# Spectroscilloscope_Revised_7.net
KiCad netlist of a schematic drawn in EAGLE
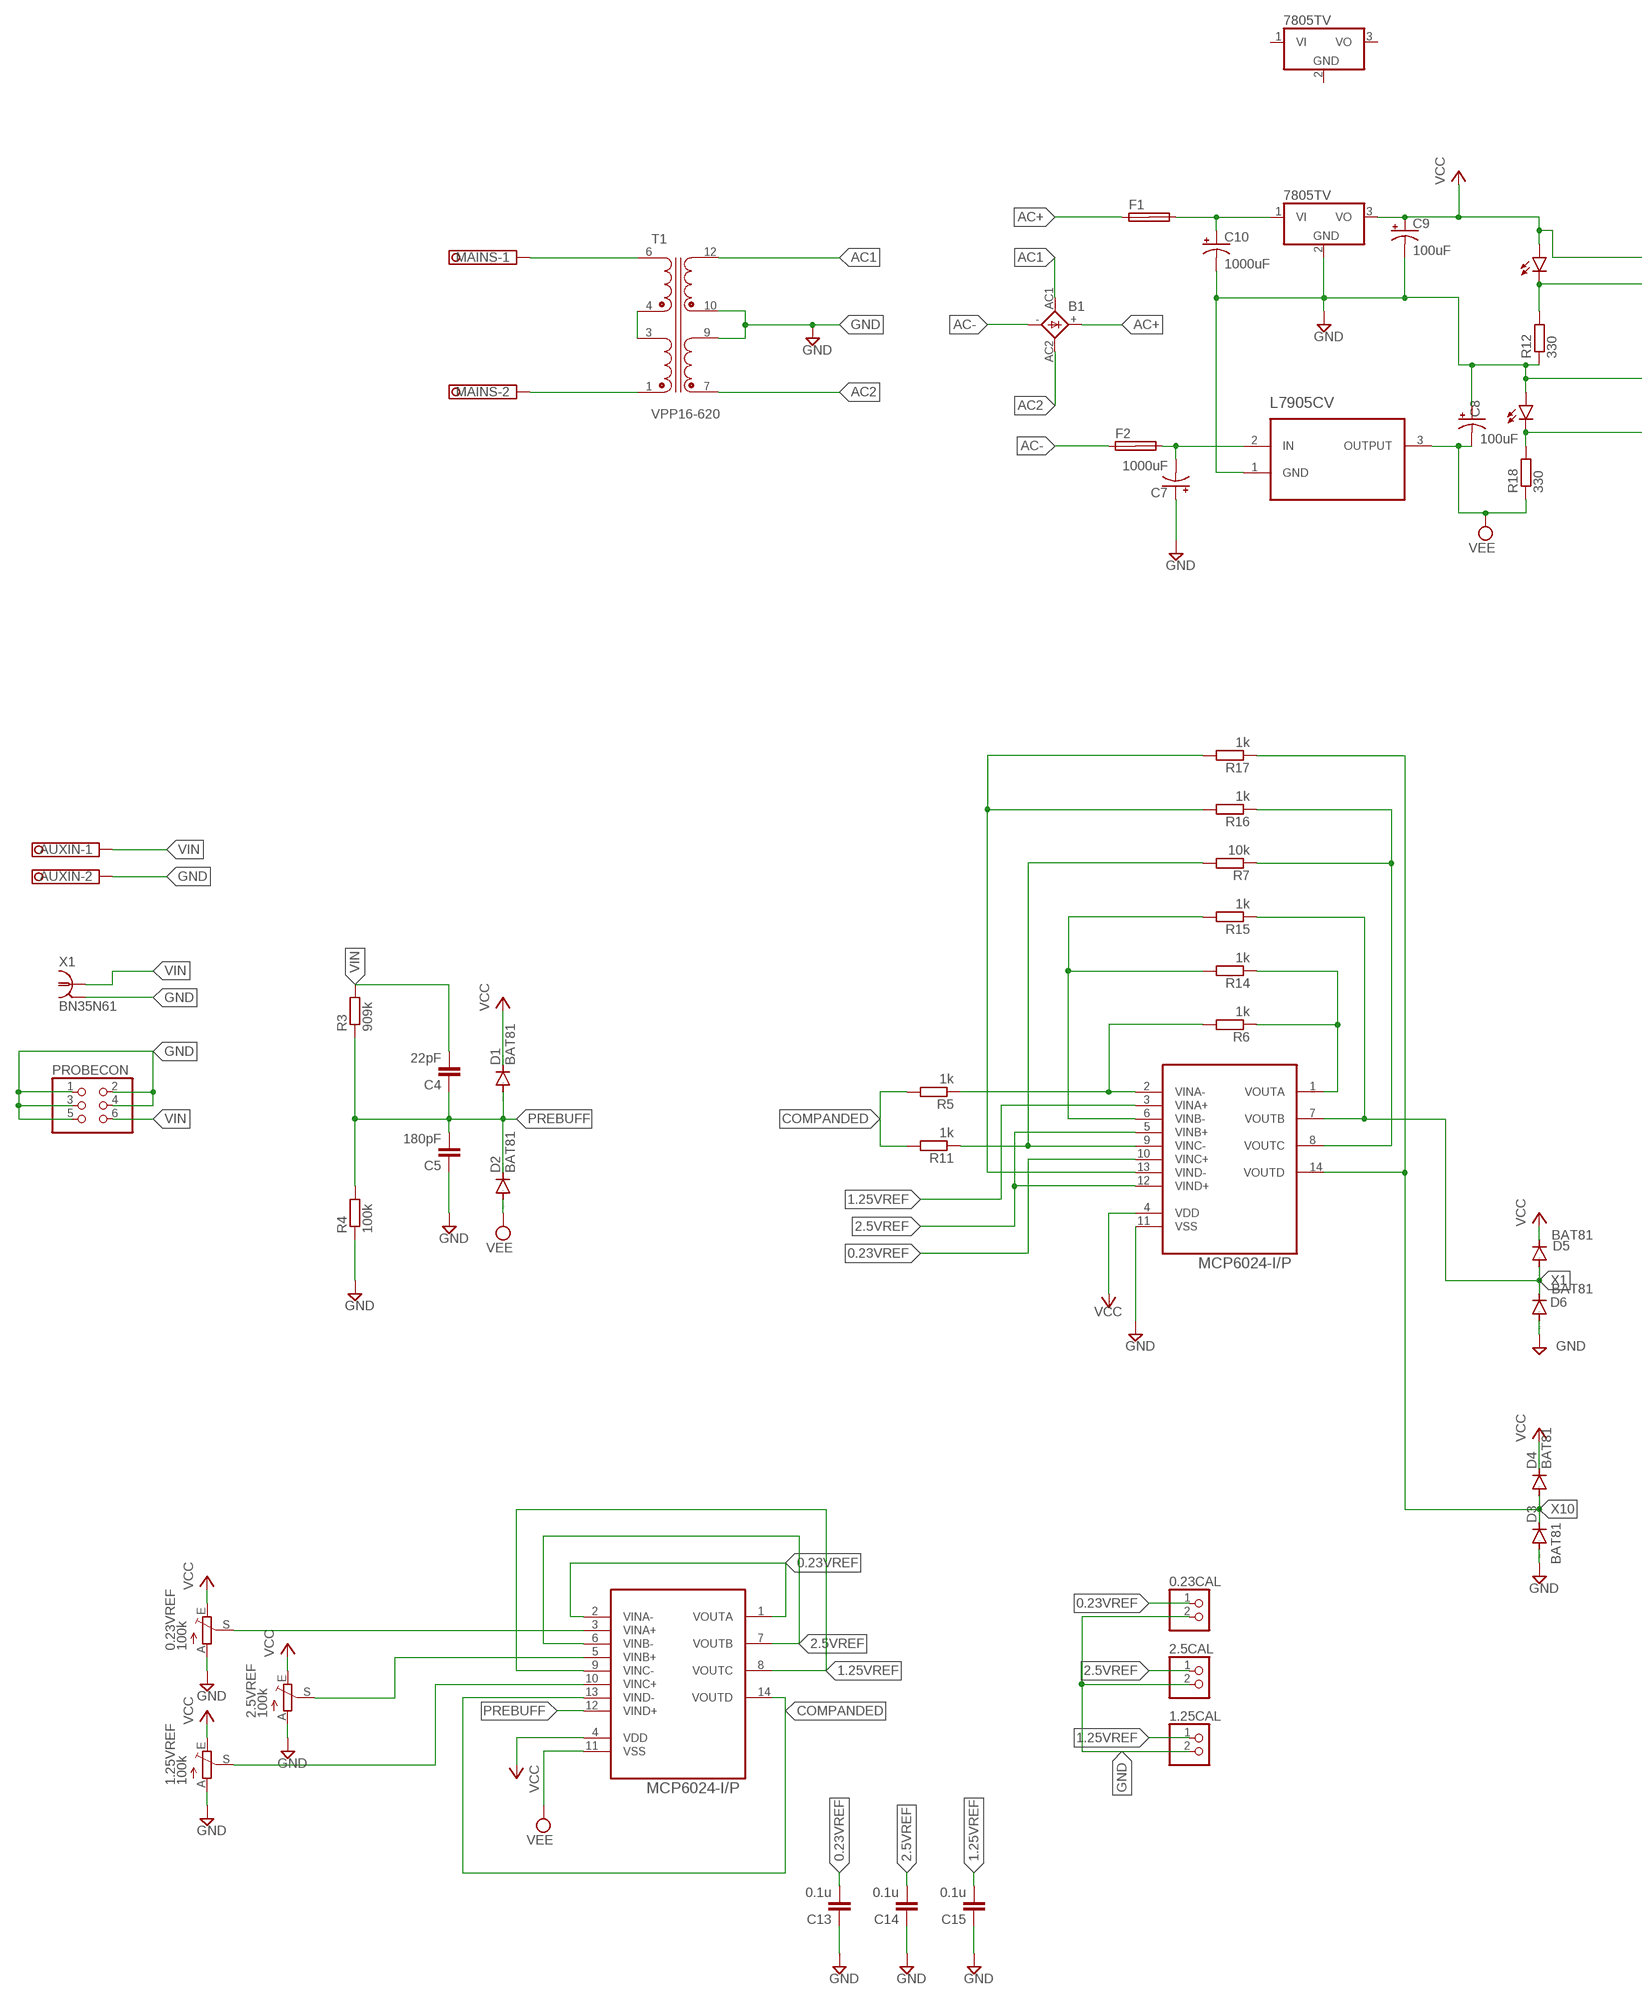
[diagram p0: schematic, sheet 1, part 1 of 2]
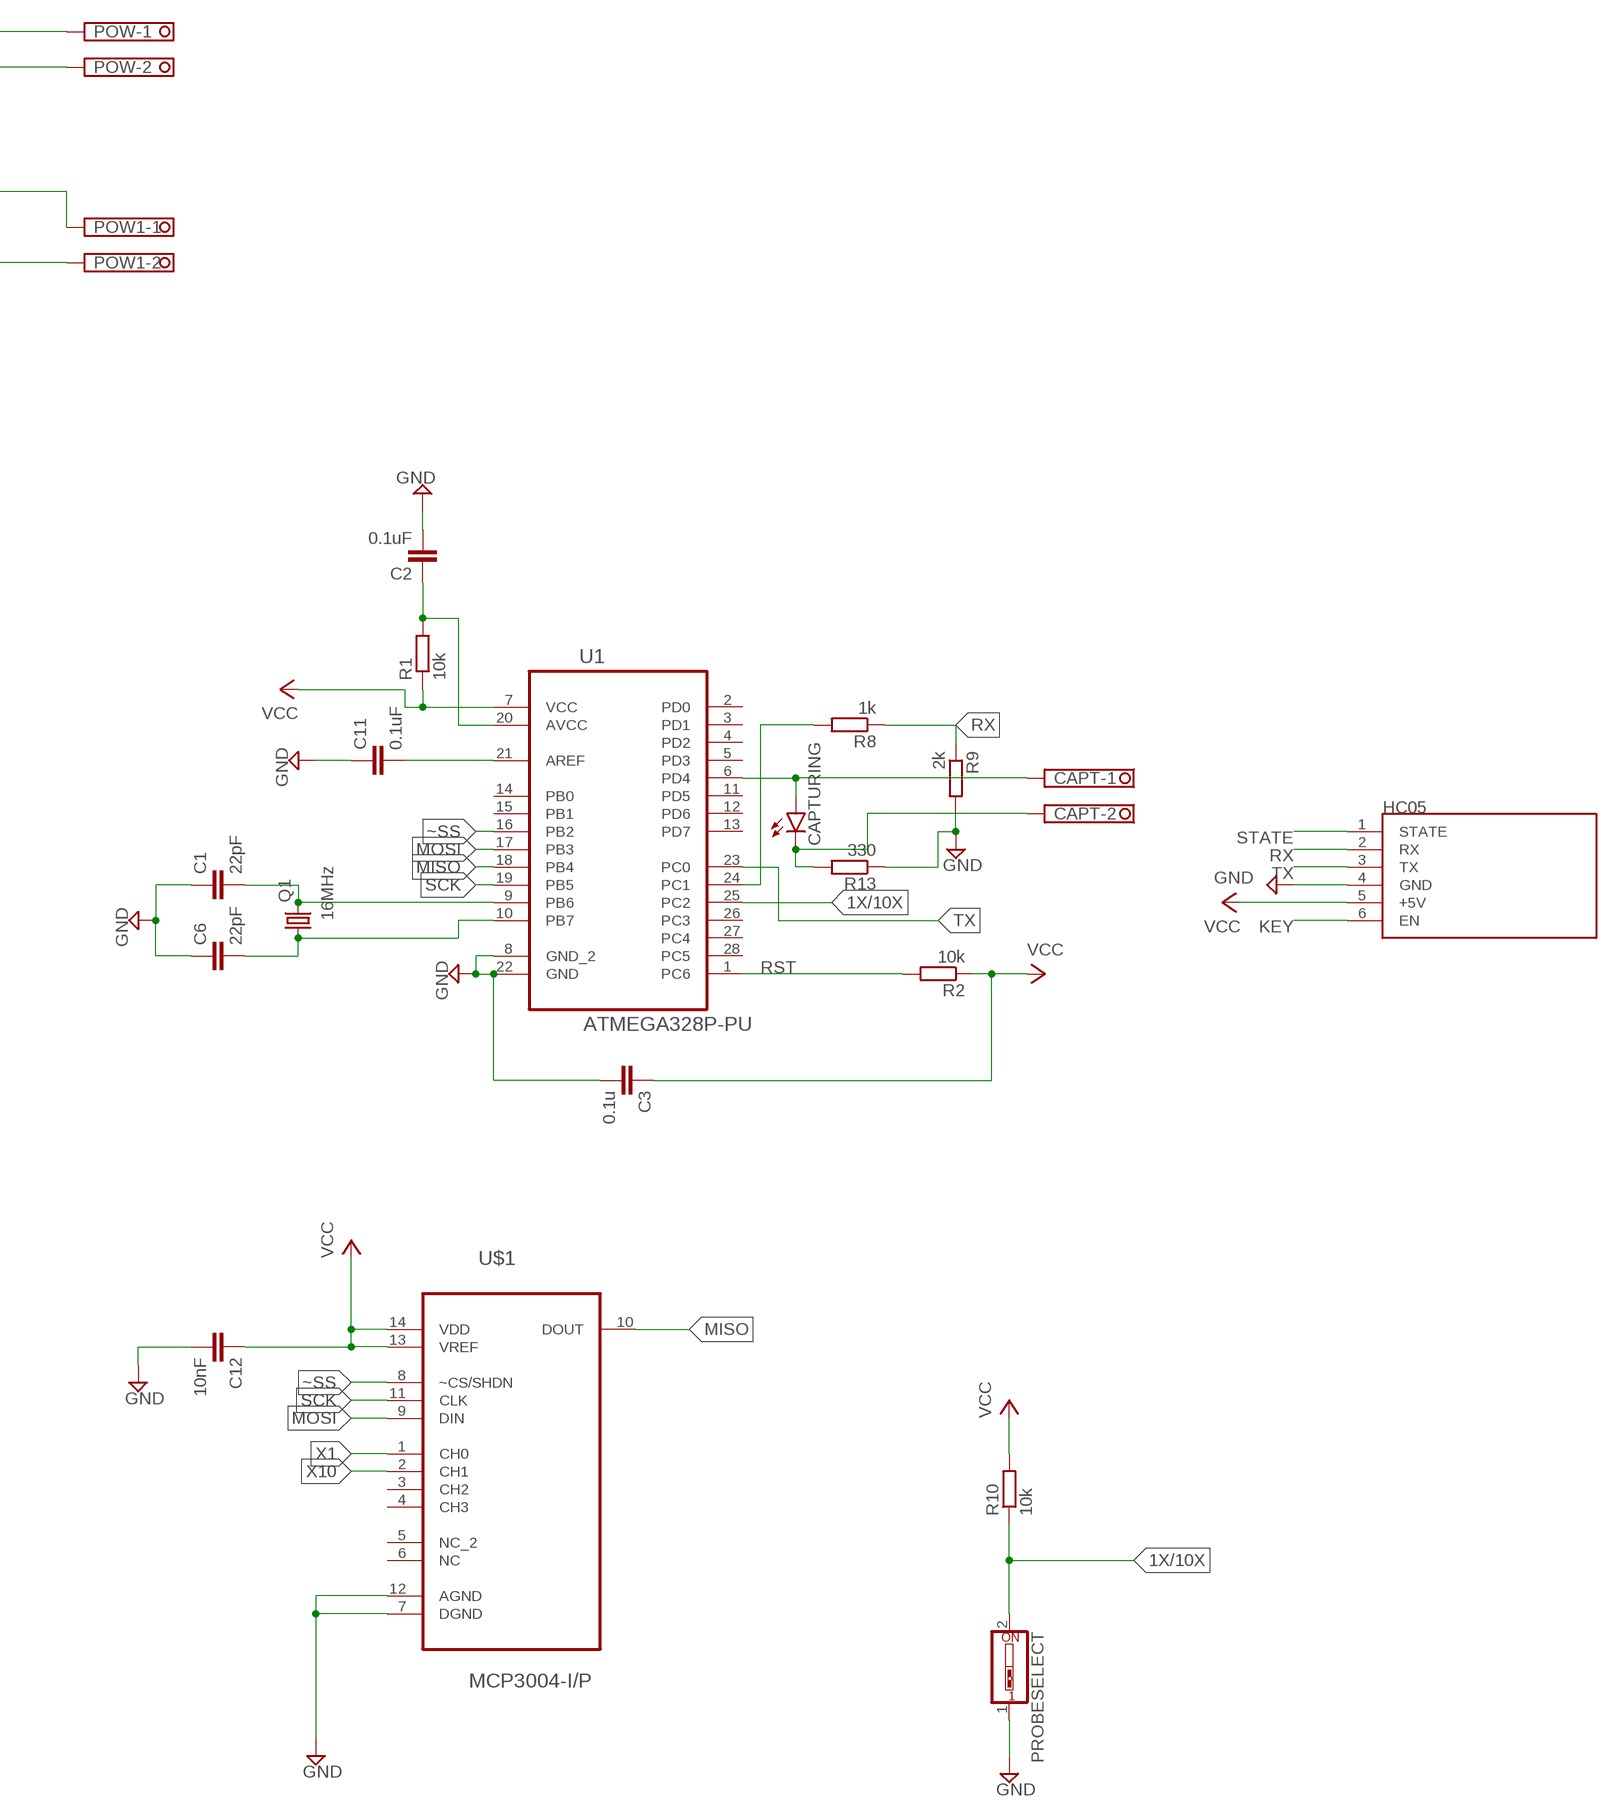
[diagram p1: schematic, sheet 1, part 2 of 2]

(export (version "E")
  (design (tool "Eeschema 10.0.6"))
  (components
    (comp (ref "0.23CAL")
      (value "PINHD-1X2")
      (footprint "eagle-import:1X02")
      (libsource (lib "eagle-import") (part "PINHD-1X2"))
    )
    (comp (ref "0.23VREF")
      (value "100k")
      (footprint "eagle-import:B25P")
      (libsource (lib "eagle-import") (part "TRIM_EU-B25P"))
    )
    (comp (ref "1.25CAL")
      (value "PINHD-1X2")
      (footprint "eagle-import:1X02")
      (libsource (lib "eagle-import") (part "PINHD-1X2"))
    )
    (comp (ref "1.25VREF")
      (value "100k")
      (footprint "eagle-import:B25P")
      (libsource (lib "eagle-import") (part "TRIM_EU-B25P"))
    )
    (comp (ref "2.5CAL")
      (value "PINHD-1X2")
      (footprint "eagle-import:1X02")
      (libsource (lib "eagle-import") (part "PINHD-1X2"))
    )
    (comp (ref "2.5VREF")
      (value "100k")
      (footprint "eagle-import:B25P")
      (libsource (lib "eagle-import") (part "TRIM_EU-B25P"))
    )
    (comp (ref "AUXIN")
      (value "TERMINAL-BLOCK-3.5MM-2-PIN-LONG-PAD")
      (footprint "eagle-import:TERMINAL-BLOCK-2-PIN-3.5MM-LONG-PAD")
      (libsource (lib "eagle-import") (part "TERMINAL-BLOCK-3.5MM-2-PIN-LONG-PAD"))
    )
    (comp (ref "B1")
      (value "2KBP")
      (footprint "eagle-import:2KBP")
      (libsource (lib "eagle-import") (part "2KBP"))
    )
    (comp (ref "C1")
      (value "22pF")
      (footprint "eagle-import:C050-024X044")
      (libsource (lib "eagle-import") (part "C-EU050-024X044"))
    )
    (comp (ref "C2")
      (value "0.1uF")
      (footprint "eagle-import:C050-024X044")
      (libsource (lib "eagle-import") (part "C-EU050-024X044"))
    )
    (comp (ref "C3")
      (value "0.1u")
      (footprint "eagle-import:C050-024X044")
      (libsource (lib "eagle-import") (part "C-EU050-024X044"))
    )
    (comp (ref "C4")
      (value "22pF")
      (footprint "eagle-import:C050-024X044")
      (libsource (lib "eagle-import") (part "C-EU050-024X044"))
    )
    (comp (ref "C5")
      (value "180pF")
      (footprint "eagle-import:C050-024X044")
      (libsource (lib "eagle-import") (part "C-EU050-024X044"))
    )
    (comp (ref "C6")
      (value "22pF")
      (footprint "eagle-import:C050-024X044")
      (libsource (lib "eagle-import") (part "C-EU050-024X044"))
    )
    (comp (ref "C7")
      (value "1000uF")
      (footprint "eagle-import:E3,5-8")
      (libsource (lib "eagle-import") (part "CPOL-USE3.5-8"))
    )
    (comp (ref "C8")
      (value "100uF")
      (footprint "eagle-import:E2,5-5")
      (libsource (lib "eagle-import") (part "CPOL-USE2.5-5"))
    )
    (comp (ref "C9")
      (value "100uF")
      (footprint "eagle-import:E2,5-5")
      (libsource (lib "eagle-import") (part "CPOL-USE2.5-5"))
    )
    (comp (ref "C10")
      (value "1000uF")
      (footprint "eagle-import:E3,5-8")
      (libsource (lib "eagle-import") (part "CPOL-USE3.5-8"))
    )
    (comp (ref "C11")
      (value "0.1uF")
      (footprint "eagle-import:C050-024X044")
      (libsource (lib "eagle-import") (part "C-EU050-024X044"))
    )
    (comp (ref "C12")
      (value "10nF")
      (footprint "eagle-import:C050-024X044")
      (libsource (lib "eagle-import") (part "C-EU050-024X044"))
    )
    (comp (ref "C13")
      (value "0.1u")
      (footprint "eagle-import:C050-024X044")
      (libsource (lib "eagle-import") (part "C-EU050-024X044"))
    )
    (comp (ref "C14")
      (value "0.1u")
      (footprint "eagle-import:C050-024X044")
      (libsource (lib "eagle-import") (part "C-EU050-024X044"))
    )
    (comp (ref "C15")
      (value "0.1u")
      (footprint "eagle-import:C050-024X044")
      (libsource (lib "eagle-import") (part "C-EU050-024X044"))
    )
    (comp (ref "CAPT")
      (value "TERMINAL-BLOCK-3.5MM-2-PIN-LONG-PAD")
      (footprint "eagle-import:TERMINAL-BLOCK-2-PIN-3.5MM-LONG-PAD")
      (libsource (lib "eagle-import") (part "TERMINAL-BLOCK-3.5MM-2-PIN-LONG-PAD"))
    )
    (comp (ref "CAPTURING")
      (value "LED5MM")
      (footprint "eagle-import:LED5MM")
      (libsource (lib "eagle-import") (part "LED5MM"))
    )
    (comp (ref "D1")
      (value "BAT81")
      (footprint "eagle-import:DO34-7")
      (libsource (lib "eagle-import") (part "BAT81"))
    )
    (comp (ref "D2")
      (value "BAT81")
      (footprint "eagle-import:DO34-7")
      (libsource (lib "eagle-import") (part "BAT81"))
    )
    (comp (ref "D3")
      (value "BAT81")
      (footprint "eagle-import:DO34-7")
      (libsource (lib "eagle-import") (part "BAT81"))
    )
    (comp (ref "D4")
      (value "BAT81")
      (footprint "eagle-import:DO34-7")
      (libsource (lib "eagle-import") (part "BAT81"))
    )
    (comp (ref "D5")
      (value "BAT81")
      (footprint "eagle-import:DO34-7")
      (libsource (lib "eagle-import") (part "BAT81"))
    )
    (comp (ref "D6")
      (value "BAT81")
      (footprint "eagle-import:DO34-7")
      (libsource (lib "eagle-import") (part "BAT81"))
    )
    (comp (ref "F1")
      (value "SHK20L")
      (footprint "eagle-import:SHK20L")
      (libsource (lib "eagle-import") (part "SHK20L"))
    )
    (comp (ref "F2")
      (value "SHK20L")
      (footprint "eagle-import:SHK20L")
      (libsource (lib "eagle-import") (part "SHK20L"))
    )
    (comp (ref "HC05")
      (value "WIRELESS-BLUETOOTH-HC-05")
      (footprint "eagle-import:WIRELESS-BLUETOOTH-HC-05")
      (libsource (lib "eagle-import") (part "WIRELESS-BLUETOOTH-HC-05"))
    )
    (comp (ref "IC1")
      (value "7805TV")
      (footprint "eagle-import:TO220V")
      (libsource (lib "eagle-import") (part "78TV05"))
    )
    (comp (ref "IC2")
      (value "7805TV")
      (footprint "eagle-import:TO220V")
      (libsource (lib "eagle-import") (part "78TV05"))
    )
    (comp (ref "MAINS")
      (value "TERMINAL-BLOCK-3.5MM-2-PIN-LONG-PAD")
      (footprint "eagle-import:TERMINAL-BLOCK-2-PIN-3.5MM-LONG-PAD")
      (libsource (lib "eagle-import") (part "TERMINAL-BLOCK-3.5MM-2-PIN-LONG-PAD"))
    )
    (comp (ref "POW")
      (value "TERMINAL-BLOCK-3.5MM-2-PIN-LONG-PAD")
      (footprint "eagle-import:TERMINAL-BLOCK-2-PIN-3.5MM-LONG-PAD")
      (libsource (lib "eagle-import") (part "TERMINAL-BLOCK-3.5MM-2-PIN-LONG-PAD"))
    )
    (comp (ref "POW1")
      (value "TERMINAL-BLOCK-3.5MM-2-PIN-LONG-PAD")
      (footprint "eagle-import:TERMINAL-BLOCK-2-PIN-3.5MM-LONG-PAD")
      (libsource (lib "eagle-import") (part "TERMINAL-BLOCK-3.5MM-2-PIN-LONG-PAD"))
    )
    (comp (ref "POWER")
      (value "LED5MM")
      (footprint "eagle-import:LED5MM")
      (libsource (lib "eagle-import") (part "LED5MM"))
    )
    (comp (ref "POWER1")
      (value "LED5MM")
      (footprint "eagle-import:LED5MM")
      (libsource (lib "eagle-import") (part "LED5MM"))
    )
    (comp (ref "PROBECON")
      (value "PINHD-2X3")
      (footprint "eagle-import:2X03")
      (libsource (lib "eagle-import") (part "PINHD-2X3"))
    )
    (comp (ref "PROBESELECT")
      (value "SW_DIP-1")
      (footprint "eagle-import:EDG-01")
      (libsource (lib "eagle-import") (part "SW_DIP-1"))
    )
    (comp (ref "Q1")
      (value "16MHz")
      (footprint "eagle-import:HC49U-V")
      (libsource (lib "eagle-import") (part "CRYSTALHC49U-V"))
    )
    (comp (ref "Q2")
      (value "L7905CV")
      (footprint "eagle-import:TO254P450X1020X1935-3P")
      (fields (field (name "MF") "STMicroelectronics"))
      (libsource (lib "eagle-import") (part "L7905CV"))
    )
    (comp (ref "R1")
      (value "10k")
      (footprint "eagle-import:0204_7")
      (libsource (lib "eagle-import") (part "R-EU_0204/7"))
    )
    (comp (ref "R2")
      (value "10k")
      (footprint "eagle-import:0204_7")
      (libsource (lib "eagle-import") (part "R-EU_0204/7"))
    )
    (comp (ref "R3")
      (value "909k")
      (footprint "eagle-import:0204_7")
      (libsource (lib "eagle-import") (part "R-EU_0204/7"))
    )
    (comp (ref "R4")
      (value "100k")
      (footprint "eagle-import:0204_7")
      (libsource (lib "eagle-import") (part "R-EU_0204/7"))
    )
    (comp (ref "R5")
      (value "1k")
      (footprint "eagle-import:0204_7")
      (libsource (lib "eagle-import") (part "R-EU_0204/7"))
    )
    (comp (ref "R6")
      (value "1k")
      (footprint "eagle-import:0204_7")
      (libsource (lib "eagle-import") (part "R-EU_0204/7"))
    )
    (comp (ref "R7")
      (value "10k")
      (footprint "eagle-import:0204_7")
      (libsource (lib "eagle-import") (part "R-EU_0204/7"))
    )
    (comp (ref "R8")
      (value "1k")
      (footprint "eagle-import:0204_7")
      (libsource (lib "eagle-import") (part "R-EU_0204/7"))
    )
    (comp (ref "R9")
      (value "2k")
      (footprint "eagle-import:0204_7")
      (libsource (lib "eagle-import") (part "R-EU_0204/7"))
    )
    (comp (ref "R10")
      (value "10k")
      (footprint "eagle-import:0204_7")
      (libsource (lib "eagle-import") (part "R-EU_0204/7"))
    )
    (comp (ref "R11")
      (value "1k")
      (footprint "eagle-import:0204_7")
      (libsource (lib "eagle-import") (part "R-EU_0204/7"))
    )
    (comp (ref "R12")
      (value "330")
      (footprint "eagle-import:0204_7")
      (libsource (lib "eagle-import") (part "R-EU_0204/7"))
    )
    (comp (ref "R13")
      (value "330")
      (footprint "eagle-import:0204_7")
      (libsource (lib "eagle-import") (part "R-EU_0204/7"))
    )
    (comp (ref "R14")
      (value "1k")
      (footprint "eagle-import:0204_7")
      (libsource (lib "eagle-import") (part "R-EU_0204/7"))
    )
    (comp (ref "R15")
      (value "1k")
      (footprint "eagle-import:0204_7")
      (libsource (lib "eagle-import") (part "R-EU_0204/7"))
    )
    (comp (ref "R16")
      (value "1k")
      (footprint "eagle-import:0204_7")
      (libsource (lib "eagle-import") (part "R-EU_0204/7"))
    )
    (comp (ref "R17")
      (value "1k")
      (footprint "eagle-import:0204_7")
      (libsource (lib "eagle-import") (part "R-EU_0204/7"))
    )
    (comp (ref "R18")
      (value "330")
      (footprint "eagle-import:0204_7")
      (libsource (lib "eagle-import") (part "R-EU_0204/7"))
    )
    (comp (ref "T1")
      (value "VPP16-620")
      (footprint "eagle-import:XFMR_VPP16-620")
      (fields (field (name "MF") "Triad Magnetics"))
      (libsource (lib "eagle-import") (part "VPP16-620"))
    )
    (comp (ref "U$1")
      (value "MCP3004-I/P")
      (footprint "eagle-import:DIP254P762X432-14")
      (fields (field (name "MF") "Microchip"))
      (libsource (lib "eagle-import") (part "MCP3004-I/P"))
    )
    (comp (ref "U1")
      (value "ATMEGA328P-PU")
      (footprint "eagle-import:DIP254P762X457-28")
      (fields (field (name "MF") "Microchip"))
      (libsource (lib "eagle-import") (part "ATMEGA328P-PU"))
    )
    (comp (ref "U2")
      (value "MCP6024-I/P")
      (footprint "eagle-import:DIP254P762X533-14")
      (fields (field (name "MF") "Microchip Technology"))
      (libsource (lib "eagle-import") (part "MCP6024-I/P"))
    )
    (comp (ref "U3")
      (value "MCP6024-I/P")
      (footprint "eagle-import:DIP254P762X533-14")
      (fields (field (name "MF") "Microchip Technology"))
      (libsource (lib "eagle-import") (part "MCP6024-I/P"))
    )
    (comp (ref "X1")
      (value "BN35N61")
      (footprint "eagle-import:B35N61")
      (libsource (lib "eagle-import") (part "BN35N61"))
    )
  )
  (nets
    (net (code "1") (name "/KEY") (class "Default")
      (node (ref "HC05") (pin "6") (pinfunction "EN_6") (pintype "bidirectional"))
    )
    (net (code "2") (name "/RST") (class "Default")
      (node (ref "R2") (pin "2") (pinfunction "2_2") (pintype "passive"))
      (node (ref "U1") (pin "1") (pinfunction "PC6_1") (pintype "bidirectional"))
    )
    (net (code "3") (name "/STATE") (class "Default")
      (node (ref "HC05") (pin "1") (pinfunction "STATE_1") (pintype "bidirectional"))
    )
    (net (code "4") (name "/~{SS}") (class "Default")
      (node (ref "U$1") (pin "8") (pinfunction "~{CS/SHDN}_8") (pintype "input"))
      (node (ref "U1") (pin "16") (pinfunction "PB2_16") (pintype "bidirectional"))
    )
    (net (code "5") (name "0.23VREF") (class "Default")
      (node (ref "0.23CAL") (pin "1") (pinfunction "1_1") (pintype "passive"))
      (node (ref "C13") (pin "2") (pinfunction "2_2") (pintype "passive"))
      (node (ref "U2") (pin "10") (pinfunction "VINC+_10") (pintype "input"))
      (node (ref "U3") (pin "1") (pinfunction "VOUTA_1") (pintype "output"))
      (node (ref "U3") (pin "2") (pinfunction "VINA-_2") (pintype "input"))
    )
    (net (code "6") (name "1.25VREF") (class "Default")
      (node (ref "1.25CAL") (pin "1") (pinfunction "1_1") (pintype "passive"))
      (node (ref "C15") (pin "2") (pinfunction "2_2") (pintype "passive"))
      (node (ref "U2") (pin "3") (pinfunction "VINA+_3") (pintype "input"))
      (node (ref "U3") (pin "8") (pinfunction "VOUTC_8") (pintype "output"))
      (node (ref "U3") (pin "9") (pinfunction "VINC-_9") (pintype "input"))
    )
    (net (code "7") (name "1X{slash}10X") (class "Default")
      (node (ref "PROBESELECT") (pin "2") (pinfunction "2_2") (pintype "passive"))
      (node (ref "R10") (pin "1") (pinfunction "1_1") (pintype "passive"))
      (node (ref "U1") (pin "25") (pinfunction "PC2_25") (pintype "bidirectional"))
    )
    (net (code "8") (name "2.5VREF") (class "Default")
      (node (ref "2.5CAL") (pin "1") (pinfunction "1_1") (pintype "passive"))
      (node (ref "C14") (pin "2") (pinfunction "2_2") (pintype "passive"))
      (node (ref "U2") (pin "12") (pinfunction "VIND+_12") (pintype "input"))
      (node (ref "U2") (pin "5") (pinfunction "VINB+_5") (pintype "input"))
      (node (ref "U3") (pin "6") (pinfunction "VINB-_6") (pintype "input"))
      (node (ref "U3") (pin "7") (pinfunction "VOUTB_7") (pintype "output"))
    )
    (net (code "9") (name "AC+") (class "Default")
      (node (ref "B1") (pin "+") (pinfunction "+_+") (pintype "passive"))
      (node (ref "F1") (pin "1A") (pinfunction "1A_1A") (pintype "passive"))
    )
    (net (code "10") (name "AC-") (class "Default")
      (node (ref "B1") (pin "-") (pinfunction "-_-") (pintype "passive"))
      (node (ref "F2") (pin "1A") (pinfunction "1A_1A") (pintype "passive"))
    )
    (net (code "11") (name "AC1") (class "Default")
      (node (ref "B1") (pin "AC1") (pinfunction "AC1_AC1") (pintype "passive"))
      (node (ref "T1") (pin "12") (pinfunction "12_12") (pintype "passive"))
    )
    (net (code "12") (name "AC2") (class "Default")
      (node (ref "B1") (pin "AC2") (pinfunction "AC2_AC2") (pintype "passive"))
      (node (ref "T1") (pin "7") (pinfunction "7_7") (pintype "passive"))
    )
    (net (code "13") (name "COMPANDED") (class "Default")
      (node (ref "R11") (pin "2") (pinfunction "2_2") (pintype "passive"))
      (node (ref "R5") (pin "2") (pinfunction "2_2") (pintype "passive"))
      (node (ref "U3") (pin "13") (pinfunction "VIND-_13") (pintype "input"))
      (node (ref "U3") (pin "14") (pinfunction "VOUTD_14") (pintype "output"))
    )
    (net (code "14") (name "GND") (class "Default")
      (node (ref "0.23CAL") (pin "2") (pinfunction "2_2") (pintype "passive"))
      (node (ref "0.23VREF") (pin "A") (pinfunction "A_A") (pintype "passive"))
      (node (ref "1.25CAL") (pin "2") (pinfunction "2_2") (pintype "passive"))
      (node (ref "1.25VREF") (pin "A") (pinfunction "A_A") (pintype "passive"))
      (node (ref "2.5CAL") (pin "2") (pinfunction "2_2") (pintype "passive"))
      (node (ref "2.5VREF") (pin "A") (pinfunction "A_A") (pintype "passive"))
      (node (ref "AUXIN") (pin "2") (pinfunction "K_2") (pintype "passive"))
      (node (ref "C1") (pin "1") (pinfunction "1_1") (pintype "passive"))
      (node (ref "C10") (pin "-") (pinfunction "-_-") (pintype "passive"))
      (node (ref "C11") (pin "1") (pinfunction "1_1") (pintype "passive"))
      (node (ref "C12") (pin "2") (pinfunction "2_2") (pintype "passive"))
      (node (ref "C13") (pin "1") (pinfunction "1_1") (pintype "passive"))
      (node (ref "C14") (pin "1") (pinfunction "1_1") (pintype "passive"))
      (node (ref "C15") (pin "1") (pinfunction "1_1") (pintype "passive"))
      (node (ref "C2") (pin "2") (pinfunction "2_2") (pintype "passive"))
      (node (ref "C3") (pin "2") (pinfunction "2_2") (pintype "passive"))
      (node (ref "C5") (pin "1") (pinfunction "1_1") (pintype "passive"))
      (node (ref "C6") (pin "1") (pinfunction "1_1") (pintype "passive"))
      (node (ref "C7") (pin "+") (pinfunction "+_+") (pintype "passive"))
      (node (ref "C8") (pin "+") (pinfunction "+_+") (pintype "passive"))
      (node (ref "C9") (pin "-") (pinfunction "-_-") (pintype "passive"))
      (node (ref "D3") (pin "A") (pinfunction "A_A") (pintype "passive"))
      (node (ref "D6") (pin "A") (pinfunction "A_A") (pintype "passive"))
      (node (ref "HC05") (pin "4") (pinfunction "GND_4") (pintype "power_in"))
      (node (ref "IC1") (pin "2") (pinfunction "GND_2") (pintype "passive"))
      (node (ref "POW1") (pin "1") (pinfunction "K_1") (pintype "passive"))
      (node (ref "POWER1") (pin "A") (pinfunction "A_A") (pintype "passive"))
      (node (ref "PROBECON") (pin "1") (pinfunction "1_1") (pintype "passive"))
      (node (ref "PROBECON") (pin "2") (pinfunction "2_2") (pintype "passive"))
      (node (ref "PROBECON") (pin "3") (pinfunction "3_3") (pintype "passive"))
      (node (ref "PROBECON") (pin "4") (pinfunction "4_4") (pintype "passive"))
      (node (ref "PROBECON") (pin "5") (pinfunction "5_5") (pintype "passive"))
      (node (ref "PROBESELECT") (pin "1") (pinfunction "1_1") (pintype "passive"))
      (node (ref "Q2") (pin "1") (pinfunction "GND_1") (pintype "passive"))
      (node (ref "R12") (pin "1") (pinfunction "1_1") (pintype "passive"))
      (node (ref "R13") (pin "1") (pinfunction "1_1") (pintype "passive"))
      (node (ref "R4") (pin "1") (pinfunction "1_1") (pintype "passive"))
      (node (ref "R9") (pin "2") (pinfunction "2_2") (pintype "passive"))
      (node (ref "T1") (pin "10") (pinfunction "10_10") (pintype "passive"))
      (node (ref "T1") (pin "9") (pinfunction "9_9") (pintype "passive"))
      (node (ref "U$1") (pin "12") (pinfunction "AGND_12") (pintype "passive"))
      (node (ref "U$1") (pin "7") (pinfunction "DGND_7") (pintype "passive"))
      (node (ref "U1") (pin "22") (pinfunction "GND_22") (pintype "passive"))
      (node (ref "U1") (pin "8") (pinfunction "GND_2_8") (pintype "passive"))
      (node (ref "U2") (pin "11") (pinfunction "VSS_11") (pintype "passive"))
      (node (ref "X1") (pin "2") (pinfunction "2_2") (pintype "passive"))
      (node (ref "X1") (pin "3") (pinfunction "2_3") (pintype "passive"))
      (node (ref "X1") (pin "4") (pinfunction "2_4") (pintype "passive"))
      (node (ref "X1") (pin "5") (pinfunction "2_5") (pintype "passive"))
    )
    (net (code "15") (name "MISO") (class "Default")
      (node (ref "U$1") (pin "10") (pinfunction "DOUT_10") (pintype "output"))
      (node (ref "U1") (pin "18") (pinfunction "PB4_18") (pintype "bidirectional"))
    )
    (net (code "16") (name "MOSI") (class "Default")
      (node (ref "U$1") (pin "9") (pinfunction "DIN_9") (pintype "input"))
      (node (ref "U1") (pin "17") (pinfunction "PB3_17") (pintype "bidirectional"))
    )
    (net (code "17") (name "Net-(CAPTA-K)") (class "Default")
      (node (ref "CAPT") (pin "1") (pinfunction "K_1") (pintype "passive"))
      (node (ref "CAPTURING") (pin "A") (pinfunction "A_A") (pintype "passive"))
      (node (ref "U1") (pin "6") (pinfunction "PD4_6") (pintype "bidirectional"))
    )
    (net (code "18") (name "Net-(CAPTB-K)") (class "Default")
      (node (ref "CAPT") (pin "2") (pinfunction "K_2") (pintype "passive"))
      (node (ref "CAPTURING") (pin "K") (pinfunction "C_K") (pintype "passive"))
      (node (ref "R13") (pin "2") (pinfunction "2_2") (pintype "passive"))
    )
    (net (code "19") (name "Net-(IC1-VI)") (class "Default")
      (node (ref "C10") (pin "+") (pinfunction "+_+") (pintype "passive"))
      (node (ref "F1") (pin "2A") (pinfunction "2A_2A") (pintype "passive"))
      (node (ref "IC1") (pin "1") (pinfunction "VI_1") (pintype "input"))
    )
    (net (code "20") (name "Net-(MAINSA-K)") (class "Default")
      (node (ref "MAINS") (pin "1") (pinfunction "K_1") (pintype "passive"))
      (node (ref "T1") (pin "6") (pinfunction "6_6") (pintype "passive"))
    )
    (net (code "21") (name "Net-(MAINSB-K)") (class "Default")
      (node (ref "MAINS") (pin "2") (pinfunction "K_2") (pintype "passive"))
      (node (ref "T1") (pin "1") (pinfunction "1_1") (pintype "passive"))
    )
    (net (code "22") (name "Net-(POW1B-K)") (class "Default")
      (node (ref "POW1") (pin "2") (pinfunction "K_2") (pintype "passive"))
      (node (ref "POWER1") (pin "K") (pinfunction "C_K") (pintype "passive"))
      (node (ref "R18") (pin "2") (pinfunction "2_2") (pintype "passive"))
    )
    (net (code "23") (name "Net-(POWB-K)") (class "Default")
      (node (ref "POW") (pin "2") (pinfunction "K_2") (pintype "passive"))
      (node (ref "POWER") (pin "K") (pinfunction "C_K") (pintype "passive"))
      (node (ref "R12") (pin "2") (pinfunction "2_2") (pintype "passive"))
    )
    (net (code "24") (name "Net-(Q2-IN)") (class "Default")
      (node (ref "C7") (pin "-") (pinfunction "-_-") (pintype "passive"))
      (node (ref "F2") (pin "2A") (pinfunction "2A_2A") (pintype "passive"))
      (node (ref "Q2") (pin "2") (pinfunction "IN_2") (pintype "input"))
    )
    (net (code "25") (name "Net-(T1-Pad3)") (class "Default")
      (node (ref "T1") (pin "3") (pinfunction "3_3") (pintype "passive"))
      (node (ref "T1") (pin "4") (pinfunction "4_4") (pintype "passive"))
    )
    (net (code "26") (name "Net-(U1-AREF)") (class "Default")
      (node (ref "C11") (pin "2") (pinfunction "2_2") (pintype "passive"))
      (node (ref "U1") (pin "21") (pinfunction "AREF_21") (pintype "input"))
    )
    (net (code "27") (name "Net-(U1-AVCC)") (class "Default")
      (node (ref "C2") (pin "1") (pinfunction "1_1") (pintype "passive"))
      (node (ref "R1") (pin "2") (pinfunction "2_2") (pintype "passive"))
      (node (ref "U1") (pin "20") (pinfunction "AVCC_20") (pintype "power_in"))
    )
    (net (code "28") (name "Net-(U1-PB6)") (class "Default")
      (node (ref "C1") (pin "2") (pinfunction "2_2") (pintype "passive"))
      (node (ref "Q1") (pin "2") (pinfunction "2_2") (pintype "passive"))
      (node (ref "U1") (pin "9") (pinfunction "PB6_9") (pintype "bidirectional"))
    )
    (net (code "29") (name "Net-(U1-PB7)") (class "Default")
      (node (ref "C6") (pin "2") (pinfunction "2_2") (pintype "passive"))
      (node (ref "Q1") (pin "1") (pinfunction "1_1") (pintype "passive"))
      (node (ref "U1") (pin "10") (pinfunction "PB7_10") (pintype "bidirectional"))
    )
    (net (code "30") (name "Net-(U1-PC1)") (class "Default")
      (node (ref "R8") (pin "2") (pinfunction "2_2") (pintype "passive"))
      (node (ref "U1") (pin "24") (pinfunction "PC1_24") (pintype "bidirectional"))
    )
    (net (code "31") (name "Net-(U2-VINA-)") (class "Default")
      (node (ref "R5") (pin "1") (pinfunction "1_1") (pintype "passive"))
      (node (ref "R6") (pin "2") (pinfunction "2_2") (pintype "passive"))
      (node (ref "U2") (pin "2") (pinfunction "VINA-_2") (pintype "input"))
    )
    (net (code "32") (name "Net-(U2-VINB-)") (class "Default")
      (node (ref "R14") (pin "2") (pinfunction "2_2") (pintype "passive"))
      (node (ref "R15") (pin "2") (pinfunction "2_2") (pintype "passive"))
      (node (ref "U2") (pin "6") (pinfunction "VINB-_6") (pintype "input"))
    )
    (net (code "33") (name "Net-(U2-VINC-)") (class "Default")
      (node (ref "R11") (pin "1") (pinfunction "1_1") (pintype "passive"))
      (node (ref "R7") (pin "2") (pinfunction "2_2") (pintype "passive"))
      (node (ref "U2") (pin "9") (pinfunction "VINC-_9") (pintype "input"))
    )
    (net (code "34") (name "Net-(U2-VIND-)") (class "Default")
      (node (ref "R16") (pin "2") (pinfunction "2_2") (pintype "passive"))
      (node (ref "R17") (pin "2") (pinfunction "2_2") (pintype "passive"))
      (node (ref "U2") (pin "13") (pinfunction "VIND-_13") (pintype "input"))
    )
    (net (code "35") (name "Net-(U2-VOUTA)") (class "Default")
      (node (ref "R14") (pin "1") (pinfunction "1_1") (pintype "passive"))
      (node (ref "R6") (pin "1") (pinfunction "1_1") (pintype "passive"))
      (node (ref "U2") (pin "1") (pinfunction "VOUTA_1") (pintype "output"))
    )
    (net (code "36") (name "Net-(U2-VOUTC)") (class "Default")
      (node (ref "R16") (pin "1") (pinfunction "1_1") (pintype "passive"))
      (node (ref "R7") (pin "1") (pinfunction "1_1") (pintype "passive"))
      (node (ref "U2") (pin "8") (pinfunction "VOUTC_8") (pintype "output"))
    )
    (net (code "37") (name "Net-(U3-VINA+)") (class "Default")
      (node (ref "0.23VREF") (pin "S") (pinfunction "S_S") (pintype "passive"))
      (node (ref "U3") (pin "3") (pinfunction "VINA+_3") (pintype "input"))
    )
    (net (code "38") (name "Net-(U3-VINB+)") (class "Default")
      (node (ref "2.5VREF") (pin "S") (pinfunction "S_S") (pintype "passive"))
      (node (ref "U3") (pin "5") (pinfunction "VINB+_5") (pintype "input"))
    )
    (net (code "39") (name "Net-(U3-VINC+)") (class "Default")
      (node (ref "1.25VREF") (pin "S") (pinfunction "S_S") (pintype "passive"))
      (node (ref "U3") (pin "10") (pinfunction "VINC+_10") (pintype "input"))
    )
    (net (code "40") (name "PREBUFF") (class "Default")
      (node (ref "C4") (pin "1") (pinfunction "1_1") (pintype "passive"))
      (node (ref "C5") (pin "2") (pinfunction "2_2") (pintype "passive"))
      (node (ref "D1") (pin "A") (pinfunction "A_A") (pintype "passive"))
      (node (ref "D2") (pin "C") (pinfunction "C_C") (pintype "passive"))
      (node (ref "R3") (pin "1") (pinfunction "1_1") (pintype "passive"))
      (node (ref "R4") (pin "2") (pinfunction "2_2") (pintype "passive"))
      (node (ref "U3") (pin "12") (pinfunction "VIND+_12") (pintype "input"))
    )
    (net (code "41") (name "RX") (class "Default")
      (node (ref "HC05") (pin "2") (pinfunction "RX_2") (pintype "bidirectional"))
      (node (ref "R8") (pin "1") (pinfunction "1_1") (pintype "passive"))
      (node (ref "R9") (pin "1") (pinfunction "1_1") (pintype "passive"))
    )
    (net (code "42") (name "SCK") (class "Default")
      (node (ref "U$1") (pin "11") (pinfunction "CLK_11") (pintype "input"))
      (node (ref "U1") (pin "19") (pinfunction "PB5_19") (pintype "bidirectional"))
    )
    (net (code "43") (name "TX") (class "Default")
      (node (ref "HC05") (pin "3") (pinfunction "TX_3") (pintype "bidirectional"))
      (node (ref "U1") (pin "23") (pinfunction "PC0_23") (pintype "bidirectional"))
    )
    (net (code "44") (name "VCC") (class "Default")
      (node (ref "0.23VREF") (pin "E") (pinfunction "E_E") (pintype "passive"))
      (node (ref "1.25VREF") (pin "E") (pinfunction "E_E") (pintype "passive"))
      (node (ref "2.5VREF") (pin "E") (pinfunction "E_E") (pintype "passive"))
      (node (ref "C12") (pin "1") (pinfunction "1_1") (pintype "passive"))
      (node (ref "C3") (pin "1") (pinfunction "1_1") (pintype "passive"))
      (node (ref "C9") (pin "+") (pinfunction "+_+") (pintype "passive"))
      (node (ref "D1") (pin "C") (pinfunction "C_C") (pintype "passive"))
      (node (ref "D4") (pin "C") (pinfunction "C_C") (pintype "passive"))
      (node (ref "D5") (pin "C") (pinfunction "C_C") (pintype "passive"))
      (node (ref "HC05") (pin "5") (pinfunction "+5V_5") (pintype "power_in"))
      (node (ref "IC1") (pin "3") (pinfunction "VO_3") (pintype "passive"))
      (node (ref "POW") (pin "1") (pinfunction "K_1") (pintype "passive"))
      (node (ref "POWER") (pin "A") (pinfunction "A_A") (pintype "passive"))
      (node (ref "R1") (pin "1") (pinfunction "1_1") (pintype "passive"))
      (node (ref "R10") (pin "2") (pinfunction "2_2") (pintype "passive"))
      (node (ref "R2") (pin "1") (pinfunction "1_1") (pintype "passive"))
      (node (ref "U$1") (pin "13") (pinfunction "VREF_13") (pintype "power_in"))
      (node (ref "U$1") (pin "14") (pinfunction "VDD_14") (pintype "power_in"))
      (node (ref "U1") (pin "7") (pinfunction "VCC_7") (pintype "power_in"))
      (node (ref "U2") (pin "4") (pinfunction "VDD_4") (pintype "power_in"))
      (node (ref "U3") (pin "4") (pinfunction "VDD_4") (pintype "power_in"))
    )
    (net (code "45") (name "VEE") (class "Default")
      (node (ref "C8") (pin "-") (pinfunction "-_-") (pintype "passive"))
      (node (ref "D2") (pin "A") (pinfunction "A_A") (pintype "passive"))
      (node (ref "Q2") (pin "3") (pinfunction "OUTPUT_3") (pintype "output"))
      (node (ref "R18") (pin "1") (pinfunction "1_1") (pintype "passive"))
      (node (ref "U3") (pin "11") (pinfunction "VSS_11") (pintype "passive"))
    )
    (net (code "46") (name "VIN") (class "Default")
      (node (ref "AUXIN") (pin "1") (pinfunction "K_1") (pintype "passive"))
      (node (ref "C4") (pin "2") (pinfunction "2_2") (pintype "passive"))
      (node (ref "PROBECON") (pin "6") (pinfunction "6_6") (pintype "passive"))
      (node (ref "R3") (pin "2") (pinfunction "2_2") (pintype "passive"))
      (node (ref "X1") (pin "1") (pinfunction "1_1") (pintype "passive"))
    )
    (net (code "47") (name "X1") (class "Default")
      (node (ref "D5") (pin "A") (pinfunction "A_A") (pintype "passive"))
      (node (ref "D6") (pin "C") (pinfunction "C_C") (pintype "passive"))
      (node (ref "R15") (pin "1") (pinfunction "1_1") (pintype "passive"))
      (node (ref "U$1") (pin "1") (pinfunction "CH0_1") (pintype "input"))
      (node (ref "U2") (pin "7") (pinfunction "VOUTB_7") (pintype "output"))
    )
    (net (code "48") (name "X10") (class "Default")
      (node (ref "D3") (pin "C") (pinfunction "C_C") (pintype "passive"))
      (node (ref "D4") (pin "A") (pinfunction "A_A") (pintype "passive"))
      (node (ref "R17") (pin "1") (pinfunction "1_1") (pintype "passive"))
      (node (ref "U$1") (pin "2") (pinfunction "CH1_2") (pintype "input"))
      (node (ref "U2") (pin "14") (pinfunction "VOUTD_14") (pintype "output"))
    )
    (net (code "49") (name "unconnected-(F1-Pad1B)") (class "Default")
      (node (ref "F1") (pin "1B") (pinfunction "1B_1B") (pintype "passive"))
    )
    (net (code "50") (name "unconnected-(F1-Pad2B)") (class "Default")
      (node (ref "F1") (pin "2B") (pinfunction "2B_2B") (pintype "passive"))
    )
    (net (code "51") (name "unconnected-(F2-Pad1B)") (class "Default")
      (node (ref "F2") (pin "1B") (pinfunction "1B_1B") (pintype "passive"))
    )
    (net (code "52") (name "unconnected-(F2-Pad2B)") (class "Default")
      (node (ref "F2") (pin "2B") (pinfunction "2B_2B") (pintype "passive"))
    )
    (net (code "53") (name "unconnected-(IC2-GND-Pad2)") (class "Default")
      (node (ref "IC2") (pin "2") (pinfunction "GND_2") (pintype "passive"))
    )
    (net (code "54") (name "unconnected-(IC2-VI-Pad1)") (class "Default")
      (node (ref "IC2") (pin "1") (pinfunction "VI_1") (pintype "input"))
    )
    (net (code "55") (name "unconnected-(IC2-VO-Pad3)") (class "Default")
      (node (ref "IC2") (pin "3") (pinfunction "VO_3") (pintype "passive"))
    )
    (net (code "56") (name "unconnected-(U$1-CH2-Pad3)") (class "Default")
      (node (ref "U$1") (pin "3") (pinfunction "CH2_3") (pintype "input"))
    )
    (net (code "57") (name "unconnected-(U$1-CH3-Pad4)") (class "Default")
      (node (ref "U$1") (pin "4") (pinfunction "CH3_4") (pintype "input"))
    )
    (net (code "58") (name "unconnected-(U$1-NC-Pad6)") (class "Default")
      (node (ref "U$1") (pin "6") (pinfunction "NC_6") (pintype "no_connect"))
    )
    (net (code "59") (name "unconnected-(U$1-NC_2-Pad5)") (class "Default")
      (node (ref "U$1") (pin "5") (pinfunction "NC_2_5") (pintype "no_connect"))
    )
    (net (code "60") (name "unconnected-(U1-PB0-Pad14)") (class "Default")
      (node (ref "U1") (pin "14") (pinfunction "PB0_14") (pintype "bidirectional"))
    )
    (net (code "61") (name "unconnected-(U1-PB1-Pad15)") (class "Default")
      (node (ref "U1") (pin "15") (pinfunction "PB1_15") (pintype "bidirectional"))
    )
    (net (code "62") (name "unconnected-(U1-PC3-Pad26)") (class "Default")
      (node (ref "U1") (pin "26") (pinfunction "PC3_26") (pintype "bidirectional"))
    )
    (net (code "63") (name "unconnected-(U1-PC4-Pad27)") (class "Default")
      (node (ref "U1") (pin "27") (pinfunction "PC4_27") (pintype "bidirectional"))
    )
    (net (code "64") (name "unconnected-(U1-PC5-Pad28)") (class "Default")
      (node (ref "U1") (pin "28") (pinfunction "PC5_28") (pintype "bidirectional"))
    )
    (net (code "65") (name "unconnected-(U1-PD0-Pad2)") (class "Default")
      (node (ref "U1") (pin "2") (pinfunction "PD0_2") (pintype "bidirectional"))
    )
    (net (code "66") (name "unconnected-(U1-PD1-Pad3)") (class "Default")
      (node (ref "U1") (pin "3") (pinfunction "PD1_3") (pintype "bidirectional"))
    )
    (net (code "67") (name "unconnected-(U1-PD2-Pad4)") (class "Default")
      (node (ref "U1") (pin "4") (pinfunction "PD2_4") (pintype "bidirectional"))
    )
    (net (code "68") (name "unconnected-(U1-PD3-Pad5)") (class "Default")
      (node (ref "U1") (pin "5") (pinfunction "PD3_5") (pintype "bidirectional"))
    )
    (net (code "69") (name "unconnected-(U1-PD5-Pad11)") (class "Default")
      (node (ref "U1") (pin "11") (pinfunction "PD5_11") (pintype "bidirectional"))
    )
    (net (code "70") (name "unconnected-(U1-PD6-Pad12)") (class "Default")
      (node (ref "U1") (pin "12") (pinfunction "PD6_12") (pintype "bidirectional"))
    )
    (net (code "71") (name "unconnected-(U1-PD7-Pad13)") (class "Default")
      (node (ref "U1") (pin "13") (pinfunction "PD7_13") (pintype "bidirectional"))
    )
  )
)
